# io_expander.net
KiCad netlist of a schematic drawn in Altium Designer
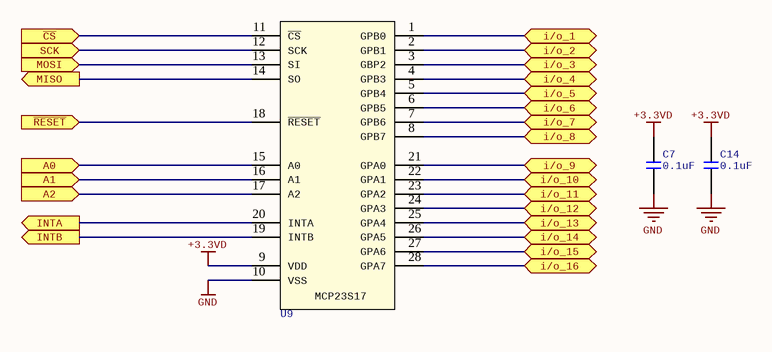
[diagram p0: io_expander.SchDoc]

(export (version "E")
  (design (tool "Eeschema 10.0.6"))
  (components
    (comp (ref "C7")
      (value "0.1uF")
      (footprint "C0603")
      (description "CAP2, CER, 0.1uF, 10%, 25V, 0603")
      (libsource (lib "stdlib") (part "VJ0603Y104KXXAC00"))
    )
    (comp (ref "C14")
      (value "0.1uF")
      (footprint "C0603")
      (description "CAP2, CER, 0.1uF, 10%, 25V, 0603")
      (libsource (lib "stdlib") (part "VJ0603Y104KXXAC00"))
    )
    (comp (ref "U9")
      (value "MCP23S17T")
      (footprint "SSOP-28")
      (description "CMOS, IC I/O EXPANDER SPI 16B 28SSOP")
      (fields
        (field (name "MANUFACTURER") "Microchip Technology")
        (field (name "MANUFACTURER PART NUMBER") "MCP23S17T-E/SS")
      )
      (libsource (lib "stdlib") (part "Microchip/MCP23S17T-E/SS"))
    )
  )
  (nets
    (net (code "1") (name "+3.3VD") (class "Default")
      (node (ref "C14") (pin "2") (pinfunction "2_2") (pintype "passive"))
      (node (ref "C7") (pin "2") (pinfunction "2_2") (pintype "passive"))
      (node (ref "U9") (pin "9") (pinfunction "VDD_9") (pintype "passive"))
    )
    (net (code "2") (name "/A0") (class "Default")
      (node (ref "U9") (pin "15") (pinfunction "A0_15") (pintype "passive"))
    )
    (net (code "3") (name "/A1") (class "Default")
      (node (ref "U9") (pin "16") (pinfunction "A1_16") (pintype "passive"))
    )
    (net (code "4") (name "/A2") (class "Default")
      (node (ref "U9") (pin "17") (pinfunction "A2_17") (pintype "passive"))
    )
    (net (code "5") (name "/INTA") (class "Default")
      (node (ref "U9") (pin "20") (pinfunction "INTA_20") (pintype "passive"))
    )
    (net (code "6") (name "/INTB") (class "Default")
      (node (ref "U9") (pin "19") (pinfunction "INTB_19") (pintype "passive"))
    )
    (net (code "7") (name "/MISO") (class "Default")
      (node (ref "U9") (pin "14") (pinfunction "SO_14") (pintype "passive"))
    )
    (net (code "8") (name "/MOSI") (class "Default")
      (node (ref "U9") (pin "13") (pinfunction "SI_13") (pintype "passive"))
    )
    (net (code "9") (name "/SCK") (class "Default")
      (node (ref "U9") (pin "12") (pinfunction "SCK_12") (pintype "passive"))
    )
    (net (code "10") (name "/i{slash}o_1") (class "Default")
      (node (ref "U9") (pin "1") (pinfunction "GPB0_1") (pintype "passive"))
    )
    (net (code "11") (name "/i{slash}o_2") (class "Default")
      (node (ref "U9") (pin "2") (pinfunction "GPB1_2") (pintype "passive"))
    )
    (net (code "12") (name "/i{slash}o_3") (class "Default")
      (node (ref "U9") (pin "3") (pinfunction "GBP2_3") (pintype "passive"))
    )
    (net (code "13") (name "/i{slash}o_4") (class "Default")
      (node (ref "U9") (pin "4") (pinfunction "GPB3_4") (pintype "passive"))
    )
    (net (code "14") (name "/i{slash}o_5") (class "Default")
      (node (ref "U9") (pin "5") (pinfunction "GPB4_5") (pintype "passive"))
    )
    (net (code "15") (name "/i{slash}o_6") (class "Default")
      (node (ref "U9") (pin "6") (pinfunction "GPB5_6") (pintype "passive"))
    )
    (net (code "16") (name "/i{slash}o_7") (class "Default")
      (node (ref "U9") (pin "7") (pinfunction "GPB6_7") (pintype "passive"))
    )
    (net (code "17") (name "/i{slash}o_8") (class "Default")
      (node (ref "U9") (pin "8") (pinfunction "GPB7_8") (pintype "passive"))
    )
    (net (code "18") (name "/i{slash}o_9") (class "Default")
      (node (ref "U9") (pin "21") (pinfunction "GPA0_21") (pintype "passive"))
    )
    (net (code "19") (name "/i{slash}o_10") (class "Default")
      (node (ref "U9") (pin "22") (pinfunction "GPA1_22") (pintype "passive"))
    )
    (net (code "20") (name "/i{slash}o_11") (class "Default")
      (node (ref "U9") (pin "23") (pinfunction "GPA2_23") (pintype "passive"))
    )
    (net (code "21") (name "/i{slash}o_12") (class "Default")
      (node (ref "U9") (pin "24") (pinfunction "GPA3_24") (pintype "passive"))
    )
    (net (code "22") (name "/i{slash}o_13") (class "Default")
      (node (ref "U9") (pin "25") (pinfunction "GPA4_25") (pintype "passive"))
    )
    (net (code "23") (name "/i{slash}o_14") (class "Default")
      (node (ref "U9") (pin "26") (pinfunction "GPA5_26") (pintype "passive"))
    )
    (net (code "24") (name "/i{slash}o_15") (class "Default")
      (node (ref "U9") (pin "27") (pinfunction "GPA6_27") (pintype "passive"))
    )
    (net (code "25") (name "/i{slash}o_16") (class "Default")
      (node (ref "U9") (pin "28") (pinfunction "GPA7_28") (pintype "passive"))
    )
    (net (code "26") (name "/~{CS}") (class "Default")
      (node (ref "U9") (pin "11") (pinfunction "~{CS}_11") (pintype "passive"))
    )
    (net (code "27") (name "/~{RESET}") (class "Default")
      (node (ref "U9") (pin "18") (pinfunction "~{RESET}_18") (pintype "passive"))
    )
    (net (code "28") (name "GND") (class "Default")
      (node (ref "C14") (pin "1") (pinfunction "5_1") (pintype "passive"))
      (node (ref "C7") (pin "1") (pinfunction "5_1") (pintype "passive"))
      (node (ref "U9") (pin "10") (pinfunction "VSS_10") (pintype "passive"))
    )
  )
)
